# 03_-_MAIN_SCHEMATIC.net
KiCad netlist of a schematic drawn in Altium Designer
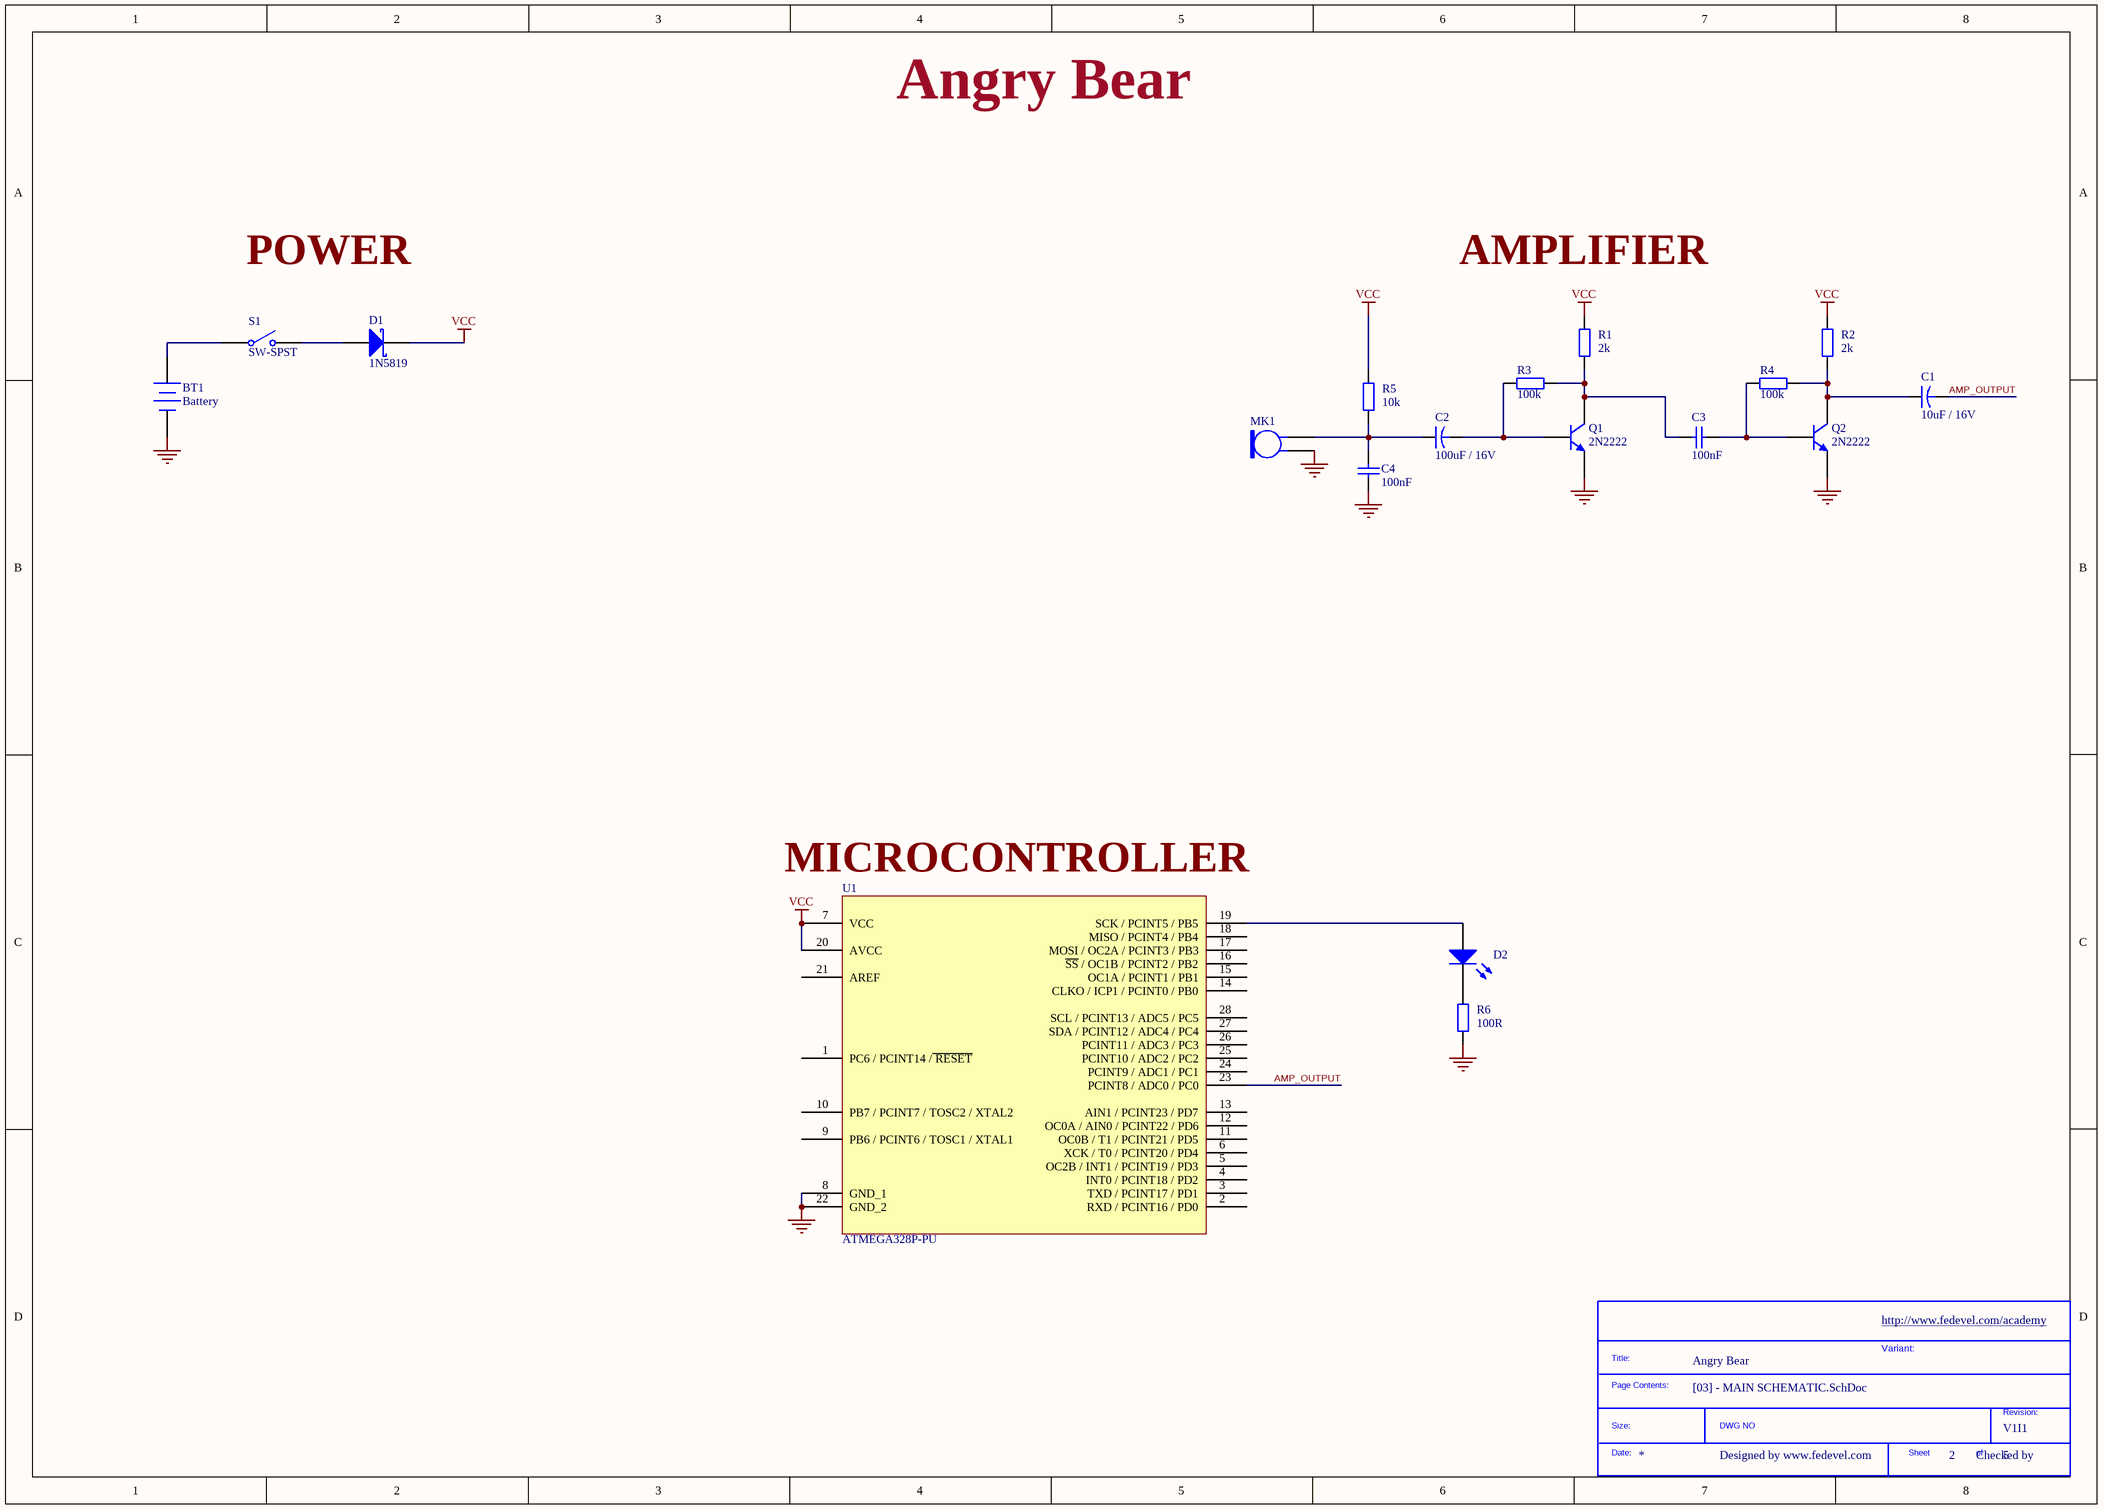
[diagram p0: [03] - MAIN SCHEMATIC.SchDoc]

(export (version "E")
  (design (tool "Eeschema 10.0.6"))
  (components
    (comp (ref "BT1")
      (value "Battery")
      (footprint "BAT-2")
      (description "Multicell Battery")
      (fields (field (name "PUBLISHER") "Altium Limited"))
      (libsource (lib "Miscellaneous Devices") (part "Battery"))
    )
    (comp (ref "C1")
      (value "10uF / 16V")
      (footprint "CAPR5-4X5")
      (description "Capacitor")
      (fields (field (name "PUBLISHER") "Altium Limited"))
      (libsource (lib "Miscellaneous Devices") (part "Cap2"))
    )
    (comp (ref "C2")
      (value "100uF / 16V")
      (footprint "CAPR5-4X5")
      (description "Capacitor")
      (fields (field (name "PUBLISHER") "Altium Limited"))
      (libsource (lib "Miscellaneous Devices") (part "Cap2"))
    )
    (comp (ref "C3")
      (value "100nF")
      (footprint "RAD-0.3")
      (description "Capacitor")
      (fields (field (name "PUBLISHER") "Altium Limited"))
      (libsource (lib "Miscellaneous Devices") (part "Cap"))
    )
    (comp (ref "C4")
      (value "100nF")
      (footprint "RAD-0.3")
      (description "Capacitor")
      (fields (field (name "PUBLISHER") "Altium Limited"))
      (libsource (lib "Miscellaneous Devices") (part "Cap"))
    )
    (comp (ref "D1")
      (value "1N5819")
      (footprint "DO-204AL")
      (description "Schottky Rectifier")
      (fields (field (name "PUBLISHER") "Altium Limited"))
      (libsource (lib "Miscellaneous Devices") (part "Diode 11DQ03"))
    )
    (comp (ref "D2")
      (value "LED0")
      (footprint "LED-0")
      (description "Typical INFRARED GaAs LED")
      (fields (field (name "PUBLISHER") "Altium Limited"))
      (libsource (lib "Miscellaneous Devices") (part "LED0"))
    )
    (comp (ref "MK1")
      (value "Mic2")
      (footprint "PIN2")
      (description "Microphone")
      (fields (field (name "PUBLISHER") "Altium Limited"))
      (libsource (lib "Miscellaneous Devices") (part "Mic2"))
    )
    (comp (ref "Q1")
      (value "2N2222")
      (footprint "TO-226-AA")
      (description "NPN Bipolar Transistor")
      (fields
        (field (name "MANUFACTURER") "ON Semiconductor")
        (field (name "MANUFACTURER PART NUMBER") "P2N2222AG")
        (field (name "PUBLISHER") "Altium Limited")
      )
      (libsource (lib "Miscellaneous Devices") (part "NPN"))
    )
    (comp (ref "Q2")
      (value "2N2222")
      (footprint "TO-226-AA")
      (description "NPN Bipolar Transistor")
      (fields
        (field (name "MANUFACTURER") "ON Semiconductor")
        (field (name "MANUFACTURER PART NUMBER") "P2N2222AG")
        (field (name "PUBLISHER") "Altium Limited")
      )
      (libsource (lib "Miscellaneous Devices") (part "NPN"))
    )
    (comp (ref "R1")
      (value "2k")
      (footprint "AXIAL-0.4")
      (description "Resistor")
      (fields (field (name "PUBLISHER") "Altium Limited"))
      (libsource (lib "Miscellaneous Devices") (part "Res2"))
    )
    (comp (ref "R2")
      (value "2k")
      (footprint "AXIAL-0.4")
      (description "Resistor")
      (fields (field (name "PUBLISHER") "Altium Limited"))
      (libsource (lib "Miscellaneous Devices") (part "Res2"))
    )
    (comp (ref "R3")
      (value "100k")
      (footprint "AXIAL-0.4")
      (description "Resistor")
      (fields (field (name "PUBLISHER") "Altium Limited"))
      (libsource (lib "") (part "Res2_1"))
    )
    (comp (ref "R4")
      (value "100k")
      (footprint "AXIAL-0.4")
      (description "Resistor")
      (fields (field (name "PUBLISHER") "Altium Limited"))
      (libsource (lib "") (part "Res2_1"))
    )
    (comp (ref "R5")
      (value "10k")
      (footprint "AXIAL-0.4")
      (description "Resistor")
      (fields (field (name "PUBLISHER") "Altium Limited"))
      (libsource (lib "Miscellaneous Devices") (part "Res2"))
    )
    (comp (ref "R6")
      (value "100R")
      (footprint "AXIAL-0.4")
      (description "Resistor")
      (fields (field (name "PUBLISHER") "Altium Limited"))
      (libsource (lib "Miscellaneous Devices") (part "Res2"))
    )
    (comp (ref "S1")
      (value "SW-SPST")
      (footprint "SPST-2")
      (description "Single-Pole, Single-Throw Switch")
      (fields (field (name "PUBLISHER") "Altium Limited"))
      (libsource (lib "Miscellaneous Devices") (part "SW-SPST"))
    )
    (comp (ref "U1")
      (value "ATMEGA328P-PU")
      (footprint "28_DIP_7.62mm")
      (description "IC MCU 8BIT 32KB FLASH 28DIP")
      (fields
        (field (name "MANUFACTURER") "Atmel")
        (field (name ".CREATOR") "MM")
        (field (name ".CHECKED PCB") "RF")
        (field (name ".CHECKED SCH") "RF")
      )
      (libsource (lib "28Pins_Project_V1I1") (part "ATMEGA328P-PU"))
    )
  )
  (nets
    (net (code "1") (name "/AMP_OUTPUT") (class "Default")
      (node (ref "C1") (pin "2") (pinfunction "2_2") (pintype "passive"))
      (node (ref "U1") (pin "23") (pinfunction "PCINT8_/_ADC0_/_PC0_23") (pintype "passive"))
    )
    (net (code "2") (name "GND") (class "Default")
      (node (ref "BT1") (pin "2") (pinfunction "-_2") (pintype "passive"))
      (node (ref "C4") (pin "1") (pinfunction "1_1") (pintype "passive"))
      (node (ref "MK1") (pin "1") (pinfunction "1_1") (pintype "passive"))
      (node (ref "Q1") (pin "3") (pinfunction "E_3") (pintype "passive"))
      (node (ref "Q2") (pin "3") (pinfunction "E_3") (pintype "passive"))
      (node (ref "R6") (pin "1") (pinfunction "1_1") (pintype "passive"))
      (node (ref "U1") (pin "22") (pinfunction "GND_2_22") (pintype "passive"))
      (node (ref "U1") (pin "8") (pinfunction "GND_1_8") (pintype "passive"))
    )
    (net (code "3") (name "Net-(BT1-+)") (class "Default")
      (node (ref "BT1") (pin "1") (pinfunction "+_1") (pintype "passive"))
      (node (ref "S1") (pin "1") (pinfunction "COMMON_1") (pintype "passive"))
    )
    (net (code "4") (name "Net-(C2-Pad1)") (class "Default")
      (node (ref "C2") (pin "1") (pinfunction "1_1") (pintype "passive"))
      (node (ref "C4") (pin "2") (pinfunction "2_2") (pintype "passive"))
      (node (ref "MK1") (pin "2") (pinfunction "2_2") (pintype "passive"))
      (node (ref "R5") (pin "1") (pinfunction "1_1") (pintype "passive"))
    )
    (net (code "5") (name "Net-(D1-A)") (class "Default")
      (node (ref "D1") (pin "1") (pinfunction "A_1") (pintype "passive"))
      (node (ref "S1") (pin "2") (pinfunction "NO_2") (pintype "passive"))
    )
    (net (code "6") (name "Net-(D2-A)") (class "Default")
      (node (ref "D2") (pin "1") (pinfunction "A_1") (pintype "passive"))
      (node (ref "U1") (pin "19") (pinfunction "SCK_/_PCINT5_/_PB5_19") (pintype "passive"))
    )
    (net (code "7") (name "Net-(D2-K)") (class "Default")
      (node (ref "D2") (pin "2") (pinfunction "K_2") (pintype "passive"))
      (node (ref "R6") (pin "2") (pinfunction "2_2") (pintype "passive"))
    )
    (net (code "8") (name "Net-(Q1-B)") (class "Default")
      (node (ref "C2") (pin "2") (pinfunction "2_2") (pintype "passive"))
      (node (ref "Q1") (pin "2") (pinfunction "B_2") (pintype "passive"))
      (node (ref "R3") (pin "1") (pinfunction "1_1") (pintype "passive"))
    )
    (net (code "9") (name "Net-(Q1-C)") (class "Default")
      (node (ref "C3") (pin "1") (pinfunction "1_1") (pintype "passive"))
      (node (ref "Q1") (pin "1") (pinfunction "C_1") (pintype "passive"))
      (node (ref "R1") (pin "1") (pinfunction "1_1") (pintype "passive"))
      (node (ref "R3") (pin "2") (pinfunction "2_2") (pintype "passive"))
    )
    (net (code "10") (name "Net-(Q2-B)") (class "Default")
      (node (ref "C3") (pin "2") (pinfunction "2_2") (pintype "passive"))
      (node (ref "Q2") (pin "2") (pinfunction "B_2") (pintype "passive"))
      (node (ref "R4") (pin "1") (pinfunction "1_1") (pintype "passive"))
    )
    (net (code "11") (name "Net-(Q2-C)") (class "Default")
      (node (ref "C1") (pin "1") (pinfunction "1_1") (pintype "passive"))
      (node (ref "Q2") (pin "1") (pinfunction "C_1") (pintype "passive"))
      (node (ref "R2") (pin "1") (pinfunction "1_1") (pintype "passive"))
      (node (ref "R4") (pin "2") (pinfunction "2_2") (pintype "passive"))
    )
    (net (code "12") (name "VCC") (class "Default")
      (node (ref "D1") (pin "2") (pinfunction "K_2") (pintype "passive"))
      (node (ref "R1") (pin "2") (pinfunction "2_2") (pintype "passive"))
      (node (ref "R2") (pin "2") (pinfunction "2_2") (pintype "passive"))
      (node (ref "R5") (pin "2") (pinfunction "2_2") (pintype "passive"))
      (node (ref "U1") (pin "20") (pinfunction "AVCC_20") (pintype "passive"))
      (node (ref "U1") (pin "7") (pinfunction "VCC_7") (pintype "passive"))
    )
    (net (code "13") (name "unconnected-(U1-AIN1_{slash}_PCINT23_{slash}_PD7-Pad13)") (class "Default")
      (node (ref "U1") (pin "13") (pinfunction "AIN1_/_PCINT23_/_PD7_13") (pintype "passive"))
    )
    (net (code "14") (name "unconnected-(U1-AREF-Pad21)") (class "Default")
      (node (ref "U1") (pin "21") (pinfunction "AREF_21") (pintype "passive"))
    )
    (net (code "15") (name "unconnected-(U1-CLKO_{slash}_ICP1_{slash}_PCINT0_{slash}_PB0-Pad14)") (class "Default")
      (node (ref "U1") (pin "14") (pinfunction "CLKO_/_ICP1_/_PCINT0_/_PB0_14") (pintype "passive"))
    )
    (net (code "16") (name "unconnected-(U1-INT0_{slash}_PCINT18_{slash}_PD2-Pad4)") (class "Default")
      (node (ref "U1") (pin "4") (pinfunction "INT0_/_PCINT18_/_PD2_4") (pintype "passive"))
    )
    (net (code "17") (name "unconnected-(U1-MISO_{slash}_PCINT4_{slash}_PB4-Pad18)") (class "Default")
      (node (ref "U1") (pin "18") (pinfunction "MISO_/_PCINT4_/_PB4_18") (pintype "passive"))
    )
    (net (code "18") (name "unconnected-(U1-MOSI_{slash}_OC2A_{slash}_PCINT3_{slash}_PB3-Pad17)") (class "Default")
      (node (ref "U1") (pin "17") (pinfunction "MOSI_/_OC2A_/_PCINT3_/_PB3_17") (pintype "passive"))
    )
    (net (code "19") (name "unconnected-(U1-OC0A_{slash}_AIN0_{slash}_PCINT22_{slash}_PD6-Pad12)") (class "Default")
      (node (ref "U1") (pin "12") (pinfunction "OC0A_/_AIN0_/_PCINT22_/_PD6_12") (pintype "passive"))
    )
    (net (code "20") (name "unconnected-(U1-OC0B_{slash}_T1_{slash}_PCINT21_{slash}_PD5-Pad11)") (class "Default")
      (node (ref "U1") (pin "11") (pinfunction "OC0B_/_T1_/_PCINT21_/_PD5_11") (pintype "passive"))
    )
    (net (code "21") (name "unconnected-(U1-OC1A_{slash}_PCINT1_{slash}_PB1-Pad15)") (class "Default")
      (node (ref "U1") (pin "15") (pinfunction "OC1A_/_PCINT1_/_PB1_15") (pintype "passive"))
    )
    (net (code "22") (name "unconnected-(U1-OC2B_{slash}_INT1_{slash}_PCINT19_{slash}_PD3-Pad5)") (class "Default")
      (node (ref "U1") (pin "5") (pinfunction "OC2B_/_INT1_/_PCINT19_/_PD3_5") (pintype "passive"))
    )
    (net (code "23") (name "unconnected-(U1-PB6_{slash}_PCINT6_{slash}_TOSC1_{slash}_XTAL1-Pad9)") (class "Default")
      (node (ref "U1") (pin "9") (pinfunction "PB6_/_PCINT6_/_TOSC1_/_XTAL1_9") (pintype "passive"))
    )
    (net (code "24") (name "unconnected-(U1-PB7_{slash}_PCINT7_{slash}_TOSC2_{slash}_XTAL2-Pad10)") (class "Default")
      (node (ref "U1") (pin "10") (pinfunction "PB7_/_PCINT7_/_TOSC2_/_XTAL2_10") (pintype "passive"))
    )
    (net (code "25") (name "unconnected-(U1-PC6_{slash}_PCINT14_{slash}~{_RESET}-Pad1)") (class "Default")
      (node (ref "U1") (pin "1") (pinfunction "PC6_/_PCINT14_/~{_RESET}_1") (pintype "passive"))
    )
    (net (code "26") (name "unconnected-(U1-PCINT9_{slash}_ADC1_{slash}_PC1-Pad24)") (class "Default")
      (node (ref "U1") (pin "24") (pinfunction "PCINT9_/_ADC1_/_PC1_24") (pintype "passive"))
    )
    (net (code "27") (name "unconnected-(U1-PCINT10_{slash}_ADC2_{slash}_PC2-Pad25)") (class "Default")
      (node (ref "U1") (pin "25") (pinfunction "PCINT10_/_ADC2_/_PC2_25") (pintype "passive"))
    )
    (net (code "28") (name "unconnected-(U1-PCINT11_{slash}_ADC3_{slash}_PC3-Pad26)") (class "Default")
      (node (ref "U1") (pin "26") (pinfunction "PCINT11_/_ADC3_/_PC3_26") (pintype "passive"))
    )
    (net (code "29") (name "unconnected-(U1-RXD_{slash}_PCINT16_{slash}_PD0-Pad2)") (class "Default")
      (node (ref "U1") (pin "2") (pinfunction "RXD_/_PCINT16_/_PD0_2") (pintype "passive"))
    )
    (net (code "30") (name "unconnected-(U1-SCL_{slash}_PCINT13_{slash}_ADC5_{slash}_PC5-Pad28)") (class "Default")
      (node (ref "U1") (pin "28") (pinfunction "SCL_/_PCINT13_/_ADC5_/_PC5_28") (pintype "passive"))
    )
    (net (code "31") (name "unconnected-(U1-SDA_{slash}_PCINT12_{slash}_ADC4_{slash}_PC4-Pad27)") (class "Default")
      (node (ref "U1") (pin "27") (pinfunction "SDA_/_PCINT12_/_ADC4_/_PC4_27") (pintype "passive"))
    )
    (net (code "32") (name "unconnected-(U1-TXD_{slash}_PCINT17_{slash}_PD1-Pad3)") (class "Default")
      (node (ref "U1") (pin "3") (pinfunction "TXD_/_PCINT17_/_PD1_3") (pintype "passive"))
    )
    (net (code "33") (name "unconnected-(U1-XCK_{slash}_T0_{slash}_PCINT20_{slash}_PD4-Pad6)") (class "Default")
      (node (ref "U1") (pin "6") (pinfunction "XCK_/_T0_/_PCINT20_/_PD4_6") (pintype "passive"))
    )
    (net (code "34") (name "unconnected-(U1-~{SS}_{slash}_OC1B_{slash}_PCINT2_{slash}_PB2-Pad16)") (class "Default")
      (node (ref "U1") (pin "16") (pinfunction "~{SS}_/_OC1B_/_PCINT2_/_PB2_16") (pintype "passive"))
    )
  )
)
